# LF_sensors.net
KiCad netlist of a schematic drawn in EAGLE
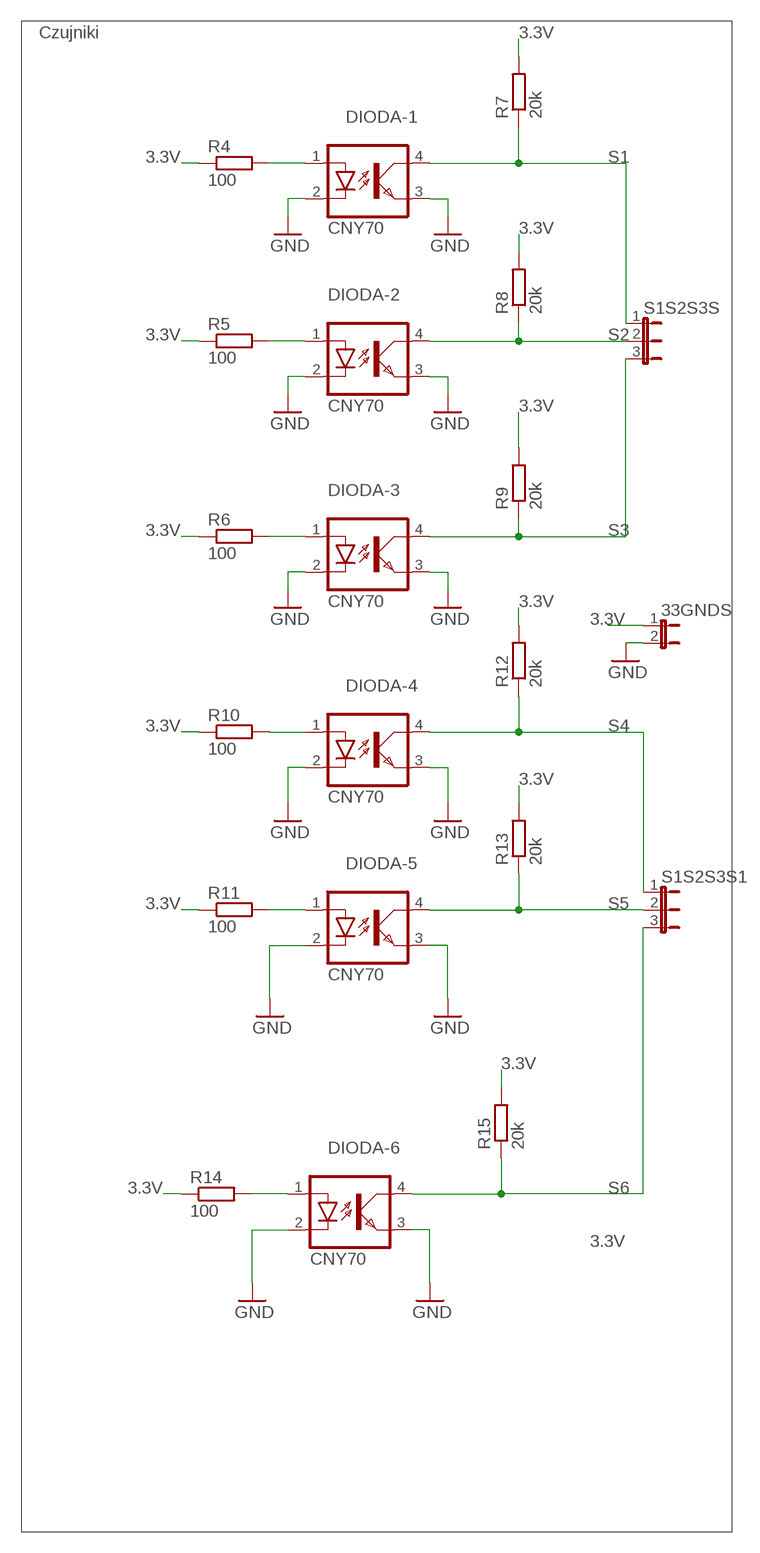
[diagram p0: schematic, sheet 1]

(export (version "E")
  (design (tool "Eeschema 10.0.6"))
  (components
    (comp (ref "33GNDS")
      (value "JP1E")
      (footprint "eagle-import:JP1")
      (libsource (lib "eagle-import") (part "JP1E"))
    )
    (comp (ref "DIODA-1")
      (value "CNY70")
      (footprint "eagle-import:DIL04")
      (libsource (lib "eagle-import") (part "LTV816"))
    )
    (comp (ref "DIODA-2")
      (value "CNY70")
      (footprint "eagle-import:DIL04")
      (libsource (lib "eagle-import") (part "LTV816"))
    )
    (comp (ref "DIODA-3")
      (value "CNY70")
      (footprint "eagle-import:DIL04")
      (libsource (lib "eagle-import") (part "LTV816"))
    )
    (comp (ref "DIODA-4")
      (value "CNY70")
      (footprint "eagle-import:DIL04")
      (libsource (lib "eagle-import") (part "LTV816"))
    )
    (comp (ref "DIODA-5")
      (value "CNY70")
      (footprint "eagle-import:DIL04")
      (libsource (lib "eagle-import") (part "LTV816"))
    )
    (comp (ref "DIODA-6")
      (value "CNY70")
      (footprint "eagle-import:DIL04")
      (libsource (lib "eagle-import") (part "LTV816"))
    )
    (comp (ref "R4")
      (value "100")
      (footprint "eagle-import:R0805")
      (libsource (lib "eagle-import") (part "R-EU_R0805"))
    )
    (comp (ref "R5")
      (value "100")
      (footprint "eagle-import:R0805")
      (libsource (lib "eagle-import") (part "R-EU_R0805"))
    )
    (comp (ref "R6")
      (value "100")
      (footprint "eagle-import:R0805")
      (libsource (lib "eagle-import") (part "R-EU_R0805"))
    )
    (comp (ref "R7")
      (value "20k")
      (footprint "eagle-import:R0805")
      (libsource (lib "eagle-import") (part "R-EU_R0805"))
    )
    (comp (ref "R8")
      (value "20k")
      (footprint "eagle-import:R0805")
      (libsource (lib "eagle-import") (part "R-EU_R0805"))
    )
    (comp (ref "R9")
      (value "20k")
      (footprint "eagle-import:R0805")
      (libsource (lib "eagle-import") (part "R-EU_R0805"))
    )
    (comp (ref "R10")
      (value "100")
      (footprint "eagle-import:R0805")
      (libsource (lib "eagle-import") (part "R-EU_R0805"))
    )
    (comp (ref "R11")
      (value "100")
      (footprint "eagle-import:R0805")
      (libsource (lib "eagle-import") (part "R-EU_R0805"))
    )
    (comp (ref "R12")
      (value "20k")
      (footprint "eagle-import:R0805")
      (libsource (lib "eagle-import") (part "R-EU_R0805"))
    )
    (comp (ref "R13")
      (value "20k")
      (footprint "eagle-import:R0805")
      (libsource (lib "eagle-import") (part "R-EU_R0805"))
    )
    (comp (ref "R14")
      (value "100")
      (footprint "eagle-import:R0805")
      (libsource (lib "eagle-import") (part "R-EU_R0805"))
    )
    (comp (ref "R15")
      (value "20k")
      (footprint "eagle-import:R0805")
      (libsource (lib "eagle-import") (part "R-EU_R0805"))
    )
    (comp (ref "S1S2S3S")
      (value "JP2E")
      (footprint "eagle-import:JP2")
      (libsource (lib "eagle-import") (part "JP2E"))
    )
    (comp (ref "S1S2S3S1")
      (value "JP2E")
      (footprint "eagle-import:JP2")
      (libsource (lib "eagle-import") (part "JP2E"))
    )
  )
  (nets
    (net (code "1") (name "/3.3V") (class "Default")
      (node (ref "33GNDS") (pin "1") (pinfunction "1_1") (pintype "passive"))
      (node (ref "R10") (pin "1") (pinfunction "1_1") (pintype "passive"))
      (node (ref "R11") (pin "1") (pinfunction "1_1") (pintype "passive"))
      (node (ref "R12") (pin "2") (pinfunction "2_2") (pintype "passive"))
      (node (ref "R13") (pin "2") (pinfunction "2_2") (pintype "passive"))
      (node (ref "R14") (pin "1") (pinfunction "1_1") (pintype "passive"))
      (node (ref "R15") (pin "2") (pinfunction "2_2") (pintype "passive"))
      (node (ref "R4") (pin "1") (pinfunction "1_1") (pintype "passive"))
      (node (ref "R5") (pin "1") (pinfunction "1_1") (pintype "passive"))
      (node (ref "R6") (pin "1") (pinfunction "1_1") (pintype "passive"))
      (node (ref "R7") (pin "2") (pinfunction "2_2") (pintype "passive"))
      (node (ref "R8") (pin "2") (pinfunction "2_2") (pintype "passive"))
      (node (ref "R9") (pin "2") (pinfunction "2_2") (pintype "passive"))
    )
    (net (code "2") (name "/S1") (class "Default")
      (node (ref "DIODA-1") (pin "4") (pinfunction "COL_4") (pintype "passive"))
      (node (ref "R7") (pin "1") (pinfunction "1_1") (pintype "passive"))
      (node (ref "S1S2S3S") (pin "1") (pinfunction "1_1") (pintype "passive"))
    )
    (net (code "3") (name "/S2") (class "Default")
      (node (ref "DIODA-2") (pin "4") (pinfunction "COL_4") (pintype "passive"))
      (node (ref "R8") (pin "1") (pinfunction "1_1") (pintype "passive"))
      (node (ref "S1S2S3S") (pin "2") (pinfunction "2_2") (pintype "passive"))
    )
    (net (code "4") (name "/S3") (class "Default")
      (node (ref "DIODA-3") (pin "4") (pinfunction "COL_4") (pintype "passive"))
      (node (ref "R9") (pin "1") (pinfunction "1_1") (pintype "passive"))
      (node (ref "S1S2S3S") (pin "3") (pinfunction "3_3") (pintype "passive"))
    )
    (net (code "5") (name "/S4") (class "Default")
      (node (ref "DIODA-4") (pin "4") (pinfunction "COL_4") (pintype "passive"))
      (node (ref "R12") (pin "1") (pinfunction "1_1") (pintype "passive"))
      (node (ref "S1S2S3S1") (pin "1") (pinfunction "1_1") (pintype "passive"))
    )
    (net (code "6") (name "/S5") (class "Default")
      (node (ref "DIODA-5") (pin "4") (pinfunction "COL_4") (pintype "passive"))
      (node (ref "R13") (pin "1") (pinfunction "1_1") (pintype "passive"))
      (node (ref "S1S2S3S1") (pin "2") (pinfunction "2_2") (pintype "passive"))
    )
    (net (code "7") (name "/S6") (class "Default")
      (node (ref "DIODA-6") (pin "4") (pinfunction "COL_4") (pintype "passive"))
      (node (ref "R15") (pin "1") (pinfunction "1_1") (pintype "passive"))
      (node (ref "S1S2S3S1") (pin "3") (pinfunction "3_3") (pintype "passive"))
    )
    (net (code "8") (name "GND") (class "Default")
      (node (ref "33GNDS") (pin "2") (pinfunction "2_2") (pintype "passive"))
      (node (ref "DIODA-1") (pin "2") (pinfunction "C_2") (pintype "passive"))
      (node (ref "DIODA-1") (pin "3") (pinfunction "EMIT_3") (pintype "passive"))
      (node (ref "DIODA-2") (pin "2") (pinfunction "C_2") (pintype "passive"))
      (node (ref "DIODA-2") (pin "3") (pinfunction "EMIT_3") (pintype "passive"))
      (node (ref "DIODA-3") (pin "2") (pinfunction "C_2") (pintype "passive"))
      (node (ref "DIODA-3") (pin "3") (pinfunction "EMIT_3") (pintype "passive"))
      (node (ref "DIODA-4") (pin "2") (pinfunction "C_2") (pintype "passive"))
      (node (ref "DIODA-4") (pin "3") (pinfunction "EMIT_3") (pintype "passive"))
      (node (ref "DIODA-5") (pin "2") (pinfunction "C_2") (pintype "passive"))
      (node (ref "DIODA-5") (pin "3") (pinfunction "EMIT_3") (pintype "passive"))
      (node (ref "DIODA-6") (pin "2") (pinfunction "C_2") (pintype "passive"))
      (node (ref "DIODA-6") (pin "3") (pinfunction "EMIT_3") (pintype "passive"))
    )
    (net (code "9") (name "Net-(DIODA-1-A)") (class "Default")
      (node (ref "DIODA-1") (pin "1") (pinfunction "A_1") (pintype "passive"))
      (node (ref "R4") (pin "2") (pinfunction "2_2") (pintype "passive"))
    )
    (net (code "10") (name "Net-(DIODA-2-A)") (class "Default")
      (node (ref "DIODA-2") (pin "1") (pinfunction "A_1") (pintype "passive"))
      (node (ref "R5") (pin "2") (pinfunction "2_2") (pintype "passive"))
    )
    (net (code "11") (name "Net-(DIODA-3-A)") (class "Default")
      (node (ref "DIODA-3") (pin "1") (pinfunction "A_1") (pintype "passive"))
      (node (ref "R6") (pin "2") (pinfunction "2_2") (pintype "passive"))
    )
    (net (code "12") (name "Net-(DIODA-4-A)") (class "Default")
      (node (ref "DIODA-4") (pin "1") (pinfunction "A_1") (pintype "passive"))
      (node (ref "R10") (pin "2") (pinfunction "2_2") (pintype "passive"))
    )
    (net (code "13") (name "Net-(DIODA-5-A)") (class "Default")
      (node (ref "DIODA-5") (pin "1") (pinfunction "A_1") (pintype "passive"))
      (node (ref "R11") (pin "2") (pinfunction "2_2") (pintype "passive"))
    )
    (net (code "14") (name "Net-(DIODA-6-A)") (class "Default")
      (node (ref "DIODA-6") (pin "1") (pinfunction "A_1") (pintype "passive"))
      (node (ref "R14") (pin "2") (pinfunction "2_2") (pintype "passive"))
    )
  )
)
